# pcb_-_vcf_et_etage_sortie_v3.net
KiCad netlist of a schematic drawn in EAGLE
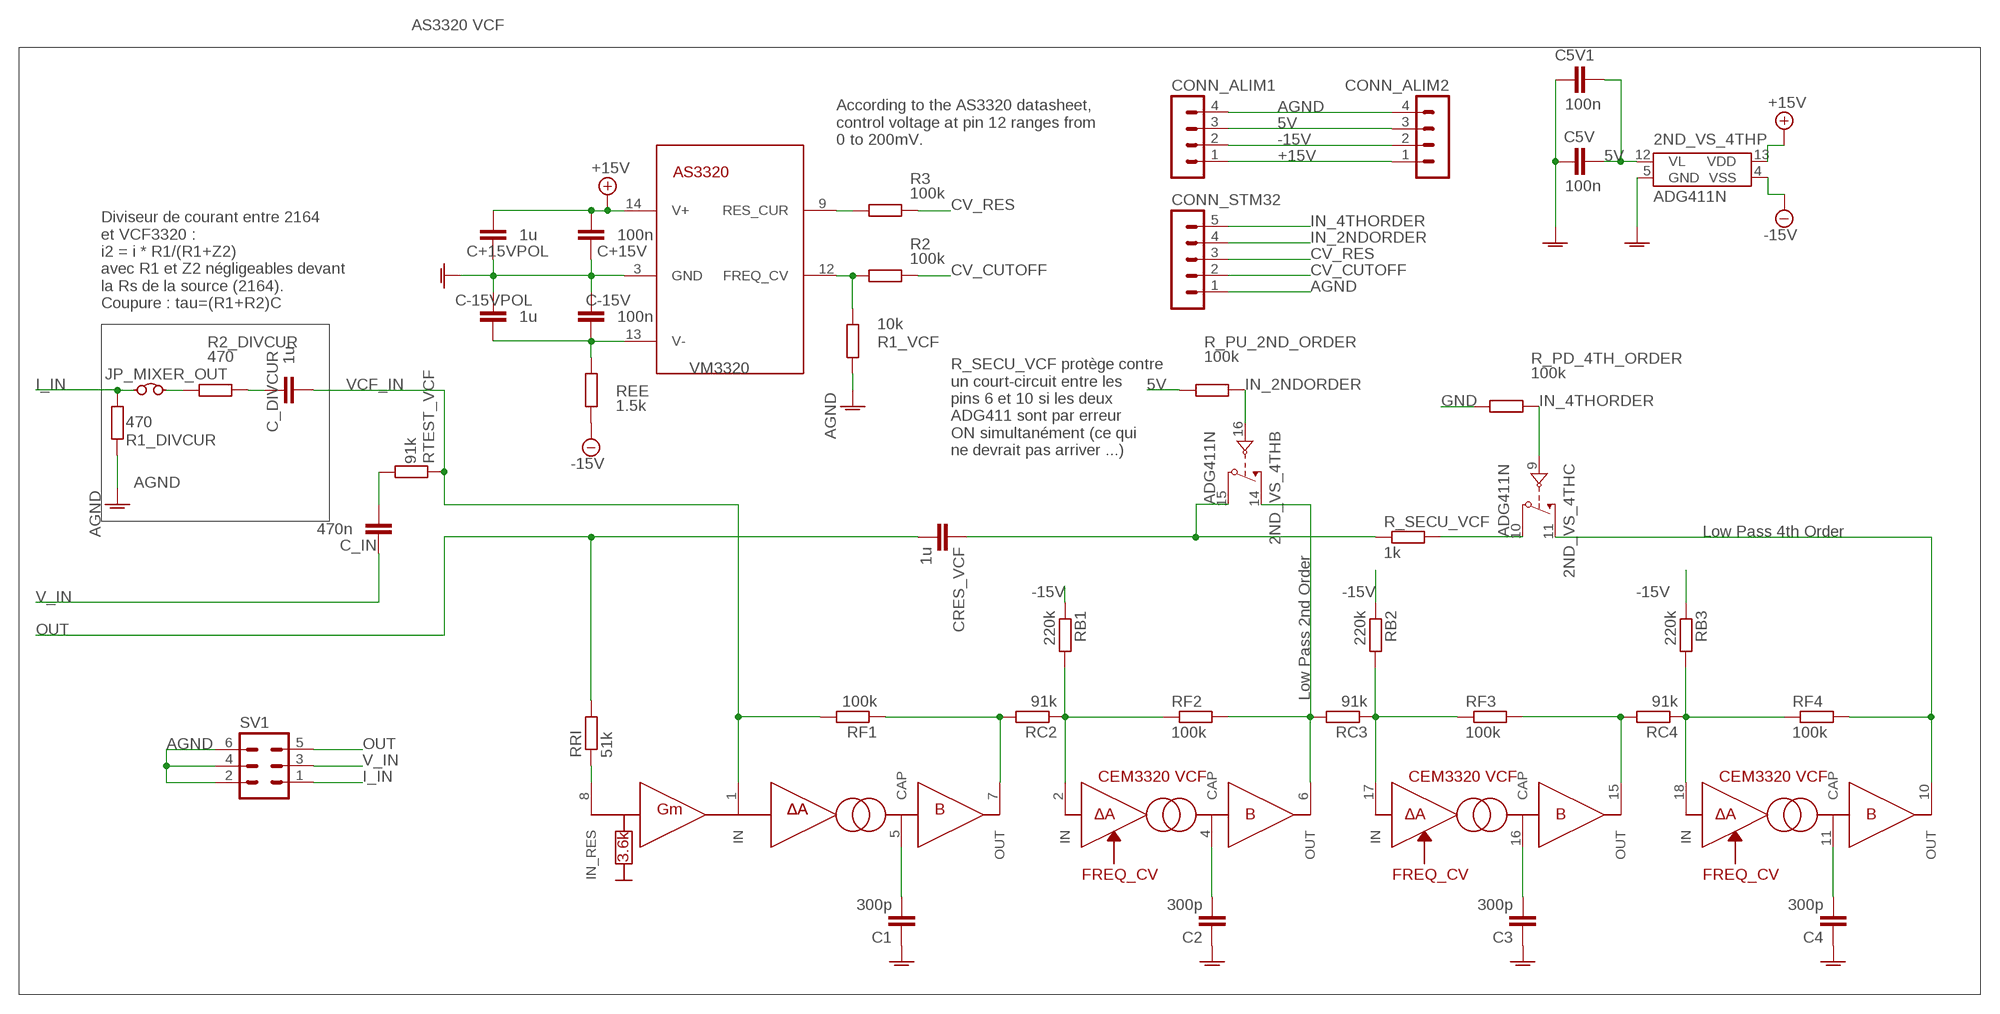
[diagram p0: schematic, sheet 1]

(export (version "E")
  (design (tool "Eeschema 10.0.6"))
  (components
    (comp (ref "2ND_VS_4TH")
      (value "ADG411N")
      (footprint "eagle-import:DIL16")
      (fields (field (name "MF") "ALTERA CORPORATION") (field (name "MPN") "ADG411BN"))
      (libsource (lib "eagle-import") (part "ADG411N"))
    )
    (comp (ref "C+15V")
      (value "100n")
      (footprint "eagle-import:C075-032X103")
      (libsource (lib "eagle-import") (part "C-EU075-032X103"))
    )
    (comp (ref "C+15VPOL")
      (value "1u")
      (footprint "eagle-import:C075-032X103")
      (libsource (lib "eagle-import") (part "C-EU075-032X103"))
    )
    (comp (ref "C-15V")
      (value "100n")
      (footprint "eagle-import:C075-032X103")
      (libsource (lib "eagle-import") (part "C-EU075-032X103"))
    )
    (comp (ref "C-15VPOL")
      (value "1u")
      (footprint "eagle-import:C075-032X103")
      (libsource (lib "eagle-import") (part "C-EU075-032X103"))
    )
    (comp (ref "C1")
      (value "300p")
      (footprint "eagle-import:C075-032X103")
      (libsource (lib "eagle-import") (part "C-EU075-032X103"))
    )
    (comp (ref "C2")
      (value "300p")
      (footprint "eagle-import:C075-032X103")
      (libsource (lib "eagle-import") (part "C-EU075-032X103"))
    )
    (comp (ref "C3")
      (value "300p")
      (footprint "eagle-import:C075-032X103")
      (libsource (lib "eagle-import") (part "C-EU075-032X103"))
    )
    (comp (ref "C4")
      (value "300p")
      (footprint "eagle-import:C075-032X103")
      (libsource (lib "eagle-import") (part "C-EU075-032X103"))
    )
    (comp (ref "C5V")
      (value "100n")
      (footprint "eagle-import:C075-032X103")
      (libsource (lib "eagle-import") (part "C-EU075-032X103"))
    )
    (comp (ref "C5V1")
      (value "100n")
      (footprint "eagle-import:C075-032X103")
      (libsource (lib "eagle-import") (part "C-EU075-032X103"))
    )
    (comp (ref "CONN_ALIM1")
      (value "MA04-1")
      (footprint "eagle-import:MA04-1")
      (libsource (lib "eagle-import") (part "MA04-1"))
    )
    (comp (ref "CONN_ALIM2")
      (value "MA04-1")
      (footprint "eagle-import:MA04-1")
      (libsource (lib "eagle-import") (part "MA04-1"))
    )
    (comp (ref "CONN_STM32")
      (value "MA05-1")
      (footprint "eagle-import:MA05-1")
      (libsource (lib "eagle-import") (part "MA05-1"))
    )
    (comp (ref "CRES_VCF")
      (value "1u")
      (footprint "eagle-import:C075-032X103")
      (libsource (lib "eagle-import") (part "C-EU075-032X103"))
    )
    (comp (ref "C_DIVCUR")
      (value "1u")
      (footprint "eagle-import:C075-032X103")
      (libsource (lib "eagle-import") (part "C-EU075-032X103"))
    )
    (comp (ref "C_IN")
      (value "470n")
      (footprint "eagle-import:C075-032X103")
      (libsource (lib "eagle-import") (part "C-EU075-032X103"))
    )
    (comp (ref "JP_MIXER_OUT")
      (value "JUMPER_WIRE")
      (footprint "eagle-import:JUMPER")
      (libsource (lib "eagle-import") (part "JUMPER_WIRE"))
    )
    (comp (ref "R1_DIVCUR")
      (value "470")
      (footprint "eagle-import:0207_10")
      (libsource (lib "eagle-import") (part "R-EU_0207/10"))
    )
    (comp (ref "R1_VCF")
      (value "10k")
      (footprint "eagle-import:0204_7")
      (libsource (lib "eagle-import") (part "R-EU_0204/7"))
    )
    (comp (ref "R2")
      (value "100k")
      (footprint "eagle-import:0204_7")
      (libsource (lib "eagle-import") (part "R-EU_0204/7"))
    )
    (comp (ref "R2_DIVCUR")
      (value "470")
      (footprint "eagle-import:0207_10")
      (libsource (lib "eagle-import") (part "R-EU_0207/10"))
    )
    (comp (ref "R3")
      (value "100k")
      (footprint "eagle-import:0204_7")
      (libsource (lib "eagle-import") (part "R-EU_0204/7"))
    )
    (comp (ref "RB1")
      (value "220k")
      (footprint "eagle-import:0207_10")
      (libsource (lib "eagle-import") (part "R-EU_0207/10"))
    )
    (comp (ref "RB2")
      (value "220k")
      (footprint "eagle-import:0204_7")
      (libsource (lib "eagle-import") (part "R-EU_0204/7"))
    )
    (comp (ref "RB3")
      (value "220k")
      (footprint "eagle-import:0204_7")
      (libsource (lib "eagle-import") (part "R-EU_0204/7"))
    )
    (comp (ref "RC2")
      (value "91k")
      (footprint "eagle-import:0204_7")
      (libsource (lib "eagle-import") (part "R-EU_0204/7"))
    )
    (comp (ref "RC3")
      (value "91k")
      (footprint "eagle-import:0204_7")
      (libsource (lib "eagle-import") (part "R-EU_0204/7"))
    )
    (comp (ref "RC4")
      (value "91k")
      (footprint "eagle-import:0204_7")
      (libsource (lib "eagle-import") (part "R-EU_0204/7"))
    )
    (comp (ref "REE")
      (value "1.5k")
      (footprint "eagle-import:0207_10")
      (libsource (lib "eagle-import") (part "R-EU_0207/10"))
    )
    (comp (ref "RF1")
      (value "100k")
      (footprint "eagle-import:0207_10")
      (libsource (lib "eagle-import") (part "R-EU_0207/10"))
    )
    (comp (ref "RF2")
      (value "100k")
      (footprint "eagle-import:0204_7")
      (libsource (lib "eagle-import") (part "R-EU_0204/7"))
    )
    (comp (ref "RF3")
      (value "100k")
      (footprint "eagle-import:0207_10")
      (libsource (lib "eagle-import") (part "R-EU_0207/10"))
    )
    (comp (ref "RF4")
      (value "100k")
      (footprint "eagle-import:0204_7")
      (libsource (lib "eagle-import") (part "R-EU_0204/7"))
    )
    (comp (ref "RRI")
      (value "51k")
      (footprint "eagle-import:0207_10")
      (libsource (lib "eagle-import") (part "R-EU_0207/10"))
    )
    (comp (ref "RTEST_VCF")
      (value "91k")
      (footprint "eagle-import:0207_10")
      (libsource (lib "eagle-import") (part "R-EU_0207/10"))
    )
    (comp (ref "R_PD_4TH_ORDER")
      (value "100k")
      (footprint "eagle-import:0204_7")
      (libsource (lib "eagle-import") (part "R-EU_0204/7"))
    )
    (comp (ref "R_PU_2ND_ORDER")
      (value "100k")
      (footprint "eagle-import:0204_7")
      (libsource (lib "eagle-import") (part "R-EU_0204/7"))
    )
    (comp (ref "R_SECU_VCF")
      (value "1k")
      (footprint "eagle-import:0204_7")
      (libsource (lib "eagle-import") (part "R-EU_0204/7"))
    )
    (comp (ref "SV1")
      (value "MA03-2")
      (footprint "eagle-import:MA03-2")
      (libsource (lib "eagle-import") (part "MA03-2"))
    )
    (comp (ref "VCF")
      (value "AS3320")
      (footprint "eagle-import:DIL18")
      (libsource (lib "eagle-import") (part "AS3320"))
    )
  )
  (nets
    (net (code "1") (name "+15V") (class "Default")
      (node (ref "2ND_VS_4TH") (pin "13") (pinfunction "VDD_13") (pintype "power_in"))
      (node (ref "C+15V") (pin "2") (pinfunction "2_2") (pintype "passive"))
      (node (ref "C+15VPOL") (pin "2") (pinfunction "2_2") (pintype "passive"))
      (node (ref "CONN_ALIM1") (pin "1") (pinfunction "1_1") (pintype "passive"))
      (node (ref "CONN_ALIM2") (pin "1") (pinfunction "1_1") (pintype "passive"))
      (node (ref "VCF") (pin "14") (pinfunction "V+_14") (pintype "bidirectional"))
    )
    (net (code "2") (name "-15V") (class "Default")
      (node (ref "2ND_VS_4TH") (pin "4") (pinfunction "VSS_4") (pintype "power_in"))
      (node (ref "CONN_ALIM1") (pin "2") (pinfunction "2_2") (pintype "passive"))
      (node (ref "CONN_ALIM2") (pin "2") (pinfunction "2_2") (pintype "passive"))
      (node (ref "RB1") (pin "1") (pinfunction "1_1") (pintype "passive"))
      (node (ref "RB2") (pin "1") (pinfunction "1_1") (pintype "passive"))
      (node (ref "RB3") (pin "1") (pinfunction "1_1") (pintype "passive"))
      (node (ref "REE") (pin "1") (pinfunction "1_1") (pintype "passive"))
    )
    (net (code "3") (name "/5V") (class "Default")
      (node (ref "2ND_VS_4TH") (pin "12") (pinfunction "VL_12") (pintype "power_in"))
      (node (ref "C5V") (pin "1") (pinfunction "1_1") (pintype "passive"))
      (node (ref "C5V1") (pin "1") (pinfunction "1_1") (pintype "passive"))
      (node (ref "CONN_ALIM1") (pin "3") (pinfunction "3_3") (pintype "passive"))
      (node (ref "CONN_ALIM2") (pin "3") (pinfunction "3_3") (pintype "passive"))
      (node (ref "R_PU_2ND_ORDER") (pin "1") (pinfunction "1_1") (pintype "passive"))
    )
    (net (code "4") (name "/CV_CUTOFF") (class "Default")
      (node (ref "CONN_STM32") (pin "2") (pinfunction "2_2") (pintype "passive"))
      (node (ref "R2") (pin "2") (pinfunction "2_2") (pintype "passive"))
    )
    (net (code "5") (name "/CV_RES") (class "Default")
      (node (ref "CONN_STM32") (pin "3") (pinfunction "3_3") (pintype "passive"))
      (node (ref "R3") (pin "2") (pinfunction "2_2") (pintype "passive"))
    )
    (net (code "6") (name "/GND") (class "Default")
      (node (ref "R_PD_4TH_ORDER") (pin "1") (pinfunction "1_1") (pintype "passive"))
    )
    (net (code "7") (name "/IN_2NDORDER") (class "Default")
      (node (ref "2ND_VS_4TH") (pin "16") (pinfunction "IN_16") (pintype "input"))
      (node (ref "CONN_STM32") (pin "4") (pinfunction "4_4") (pintype "passive"))
      (node (ref "R_PU_2ND_ORDER") (pin "2") (pinfunction "2_2") (pintype "passive"))
    )
    (net (code "8") (name "/IN_4THORDER") (class "Default")
      (node (ref "2ND_VS_4TH") (pin "9") (pinfunction "IN_9") (pintype "input"))
      (node (ref "CONN_STM32") (pin "5") (pinfunction "5_5") (pintype "passive"))
      (node (ref "R_PD_4TH_ORDER") (pin "2") (pinfunction "2_2") (pintype "passive"))
    )
    (net (code "9") (name "/I_IN") (class "Default")
      (node (ref "JP_MIXER_OUT") (pin "1") (pinfunction "1_1") (pintype "passive"))
      (node (ref "R1_DIVCUR") (pin "1") (pinfunction "1_1") (pintype "passive"))
      (node (ref "SV1") (pin "1") (pinfunction "1_1") (pintype "passive"))
    )
    (net (code "10") (name "/OUT") (class "Default")
      (node (ref "CRES_VCF") (pin "2") (pinfunction "2_2") (pintype "passive"))
      (node (ref "RRI") (pin "2") (pinfunction "2_2") (pintype "passive"))
      (node (ref "SV1") (pin "5") (pinfunction "5_5") (pintype "passive"))
    )
    (net (code "11") (name "/VCF_IN") (class "Default")
      (node (ref "C_DIVCUR") (pin "1") (pinfunction "1_1") (pintype "passive"))
      (node (ref "RF1") (pin "2") (pinfunction "2_2") (pintype "passive"))
      (node (ref "RTEST_VCF") (pin "2") (pinfunction "2_2") (pintype "passive"))
      (node (ref "VCF") (pin "1") (pinfunction "IN_1") (pintype "bidirectional"))
    )
    (net (code "12") (name "/VM3320") (class "Default")
      (node (ref "C-15V") (pin "1") (pinfunction "1_1") (pintype "passive"))
      (node (ref "C-15VPOL") (pin "1") (pinfunction "1_1") (pintype "passive"))
      (node (ref "REE") (pin "2") (pinfunction "2_2") (pintype "passive"))
      (node (ref "VCF") (pin "13") (pinfunction "V-_13") (pintype "bidirectional"))
    )
    (net (code "13") (name "/V_IN") (class "Default")
      (node (ref "C_IN") (pin "2") (pinfunction "2_2") (pintype "passive"))
      (node (ref "SV1") (pin "3") (pinfunction "3_3") (pintype "passive"))
    )
    (net (code "14") (name "AGND") (class "Default")
      (node (ref "2ND_VS_4TH") (pin "5") (pinfunction "GND_5") (pintype "power_in"))
      (node (ref "C+15V") (pin "1") (pinfunction "1_1") (pintype "passive"))
      (node (ref "C+15VPOL") (pin "1") (pinfunction "1_1") (pintype "passive"))
      (node (ref "C-15V") (pin "2") (pinfunction "2_2") (pintype "passive"))
      (node (ref "C-15VPOL") (pin "2") (pinfunction "2_2") (pintype "passive"))
      (node (ref "C1") (pin "1") (pinfunction "1_1") (pintype "passive"))
      (node (ref "C2") (pin "1") (pinfunction "1_1") (pintype "passive"))
      (node (ref "C3") (pin "1") (pinfunction "1_1") (pintype "passive"))
      (node (ref "C4") (pin "1") (pinfunction "1_1") (pintype "passive"))
      (node (ref "C5V") (pin "2") (pinfunction "2_2") (pintype "passive"))
      (node (ref "C5V1") (pin "2") (pinfunction "2_2") (pintype "passive"))
      (node (ref "CONN_ALIM1") (pin "4") (pinfunction "4_4") (pintype "passive"))
      (node (ref "CONN_ALIM2") (pin "4") (pinfunction "4_4") (pintype "passive"))
      (node (ref "CONN_STM32") (pin "1") (pinfunction "1_1") (pintype "passive"))
      (node (ref "R1_DIVCUR") (pin "2") (pinfunction "2_2") (pintype "passive"))
      (node (ref "R1_VCF") (pin "2") (pinfunction "2_2") (pintype "passive"))
      (node (ref "SV1") (pin "2") (pinfunction "2_2") (pintype "passive"))
      (node (ref "SV1") (pin "4") (pinfunction "4_4") (pintype "passive"))
      (node (ref "SV1") (pin "6") (pinfunction "6_6") (pintype "passive"))
      (node (ref "VCF") (pin "3") (pinfunction "GND_3") (pintype "bidirectional"))
    )
    (net (code "15") (name "Net-(2ND_VS_4THB-D)") (class "Default")
      (node (ref "2ND_VS_4TH") (pin "15") (pinfunction "D_15") (pintype "passive"))
      (node (ref "CRES_VCF") (pin "1") (pinfunction "1_1") (pintype "passive"))
      (node (ref "R_SECU_VCF") (pin "1") (pinfunction "1_1") (pintype "passive"))
    )
    (net (code "16") (name "Net-(2ND_VS_4THB-S)") (class "Default")
      (node (ref "2ND_VS_4TH") (pin "14") (pinfunction "S_14") (pintype "passive"))
      (node (ref "RC3") (pin "2") (pinfunction "2_2") (pintype "passive"))
      (node (ref "RF2") (pin "2") (pinfunction "2_2") (pintype "passive"))
      (node (ref "VCF") (pin "6") (pinfunction "OUT_6") (pintype "bidirectional"))
    )
    (net (code "17") (name "Net-(2ND_VS_4THC-D)") (class "Default")
      (node (ref "2ND_VS_4TH") (pin "10") (pinfunction "D_10") (pintype "passive"))
      (node (ref "R_SECU_VCF") (pin "2") (pinfunction "2_2") (pintype "passive"))
    )
    (net (code "18") (name "Net-(2ND_VS_4THC-S)") (class "Default")
      (node (ref "2ND_VS_4TH") (pin "11") (pinfunction "S_11") (pintype "passive"))
      (node (ref "RF4") (pin "2") (pinfunction "2_2") (pintype "passive"))
      (node (ref "VCF") (pin "10") (pinfunction "OUT_10") (pintype "bidirectional"))
    )
    (net (code "19") (name "Net-(C_DIVCUR-Pad2)") (class "Default")
      (node (ref "C_DIVCUR") (pin "2") (pinfunction "2_2") (pintype "passive"))
      (node (ref "R2_DIVCUR") (pin "1") (pinfunction "1_1") (pintype "passive"))
    )
    (net (code "20") (name "Net-(C_IN-Pad1)") (class "Default")
      (node (ref "C_IN") (pin "1") (pinfunction "1_1") (pintype "passive"))
      (node (ref "RTEST_VCF") (pin "1") (pinfunction "1_1") (pintype "passive"))
    )
    (net (code "21") (name "Net-(JP_MIXER_OUT-Pad2)") (class "Default")
      (node (ref "JP_MIXER_OUT") (pin "2") (pinfunction "2_2") (pintype "passive"))
      (node (ref "R2_DIVCUR") (pin "2") (pinfunction "2_2") (pintype "passive"))
    )
    (net (code "22") (name "Net-(VCFA-CAP)") (class "Default")
      (node (ref "C1") (pin "2") (pinfunction "2_2") (pintype "passive"))
      (node (ref "VCF") (pin "5") (pinfunction "CAP_5") (pintype "bidirectional"))
    )
    (net (code "23") (name "Net-(VCFA-IN_RES)") (class "Default")
      (node (ref "RRI") (pin "1") (pinfunction "1_1") (pintype "passive"))
      (node (ref "VCF") (pin "8") (pinfunction "IN_RES_8") (pintype "bidirectional"))
    )
    (net (code "24") (name "Net-(VCFA-OUT)") (class "Default")
      (node (ref "RC2") (pin "2") (pinfunction "2_2") (pintype "passive"))
      (node (ref "RF1") (pin "1") (pinfunction "1_1") (pintype "passive"))
      (node (ref "VCF") (pin "7") (pinfunction "OUT_7") (pintype "bidirectional"))
    )
    (net (code "25") (name "Net-(VCFB-CAP)") (class "Default")
      (node (ref "C2") (pin "2") (pinfunction "2_2") (pintype "passive"))
      (node (ref "VCF") (pin "4") (pinfunction "CAP_4") (pintype "bidirectional"))
    )
    (net (code "26") (name "Net-(VCFB-IN)") (class "Default")
      (node (ref "RB1") (pin "2") (pinfunction "2_2") (pintype "passive"))
      (node (ref "RC2") (pin "1") (pinfunction "1_1") (pintype "passive"))
      (node (ref "RF2") (pin "1") (pinfunction "1_1") (pintype "passive"))
      (node (ref "VCF") (pin "2") (pinfunction "IN_2") (pintype "bidirectional"))
    )
    (net (code "27") (name "Net-(VCFC-CAP)") (class "Default")
      (node (ref "C4") (pin "2") (pinfunction "2_2") (pintype "passive"))
      (node (ref "VCF") (pin "11") (pinfunction "CAP_11") (pintype "bidirectional"))
    )
    (net (code "28") (name "Net-(VCFC-IN)") (class "Default")
      (node (ref "RB3") (pin "2") (pinfunction "2_2") (pintype "passive"))
      (node (ref "RC4") (pin "1") (pinfunction "1_1") (pintype "passive"))
      (node (ref "RF4") (pin "1") (pinfunction "1_1") (pintype "passive"))
      (node (ref "VCF") (pin "18") (pinfunction "IN_18") (pintype "bidirectional"))
    )
    (net (code "29") (name "Net-(VCFD-CAP)") (class "Default")
      (node (ref "C3") (pin "2") (pinfunction "2_2") (pintype "passive"))
      (node (ref "VCF") (pin "16") (pinfunction "CAP_16") (pintype "bidirectional"))
    )
    (net (code "30") (name "Net-(VCFD-IN)") (class "Default")
      (node (ref "RB2") (pin "2") (pinfunction "2_2") (pintype "passive"))
      (node (ref "RC3") (pin "1") (pinfunction "1_1") (pintype "passive"))
      (node (ref "RF3") (pin "1") (pinfunction "1_1") (pintype "passive"))
      (node (ref "VCF") (pin "17") (pinfunction "IN_17") (pintype "bidirectional"))
    )
    (net (code "31") (name "Net-(VCFD-OUT)") (class "Default")
      (node (ref "RC4") (pin "2") (pinfunction "2_2") (pintype "passive"))
      (node (ref "RF3") (pin "2") (pinfunction "2_2") (pintype "passive"))
      (node (ref "VCF") (pin "15") (pinfunction "OUT_15") (pintype "bidirectional"))
    )
    (net (code "32") (name "Net-(VCFE-FREQ_CV)") (class "Default")
      (node (ref "R1_VCF") (pin "1") (pinfunction "1_1") (pintype "passive"))
      (node (ref "R2") (pin "1") (pinfunction "1_1") (pintype "passive"))
      (node (ref "VCF") (pin "12") (pinfunction "FREQ_CV_12") (pintype "bidirectional"))
    )
    (net (code "33") (name "Net-(VCFE-RES_CUR)") (class "Default")
      (node (ref "R3") (pin "1") (pinfunction "1_1") (pintype "passive"))
      (node (ref "VCF") (pin "9") (pinfunction "RES_CUR_9") (pintype "bidirectional"))
    )
  )
)
